# MCU.net
KiCad netlist of a schematic drawn in Altium Designer
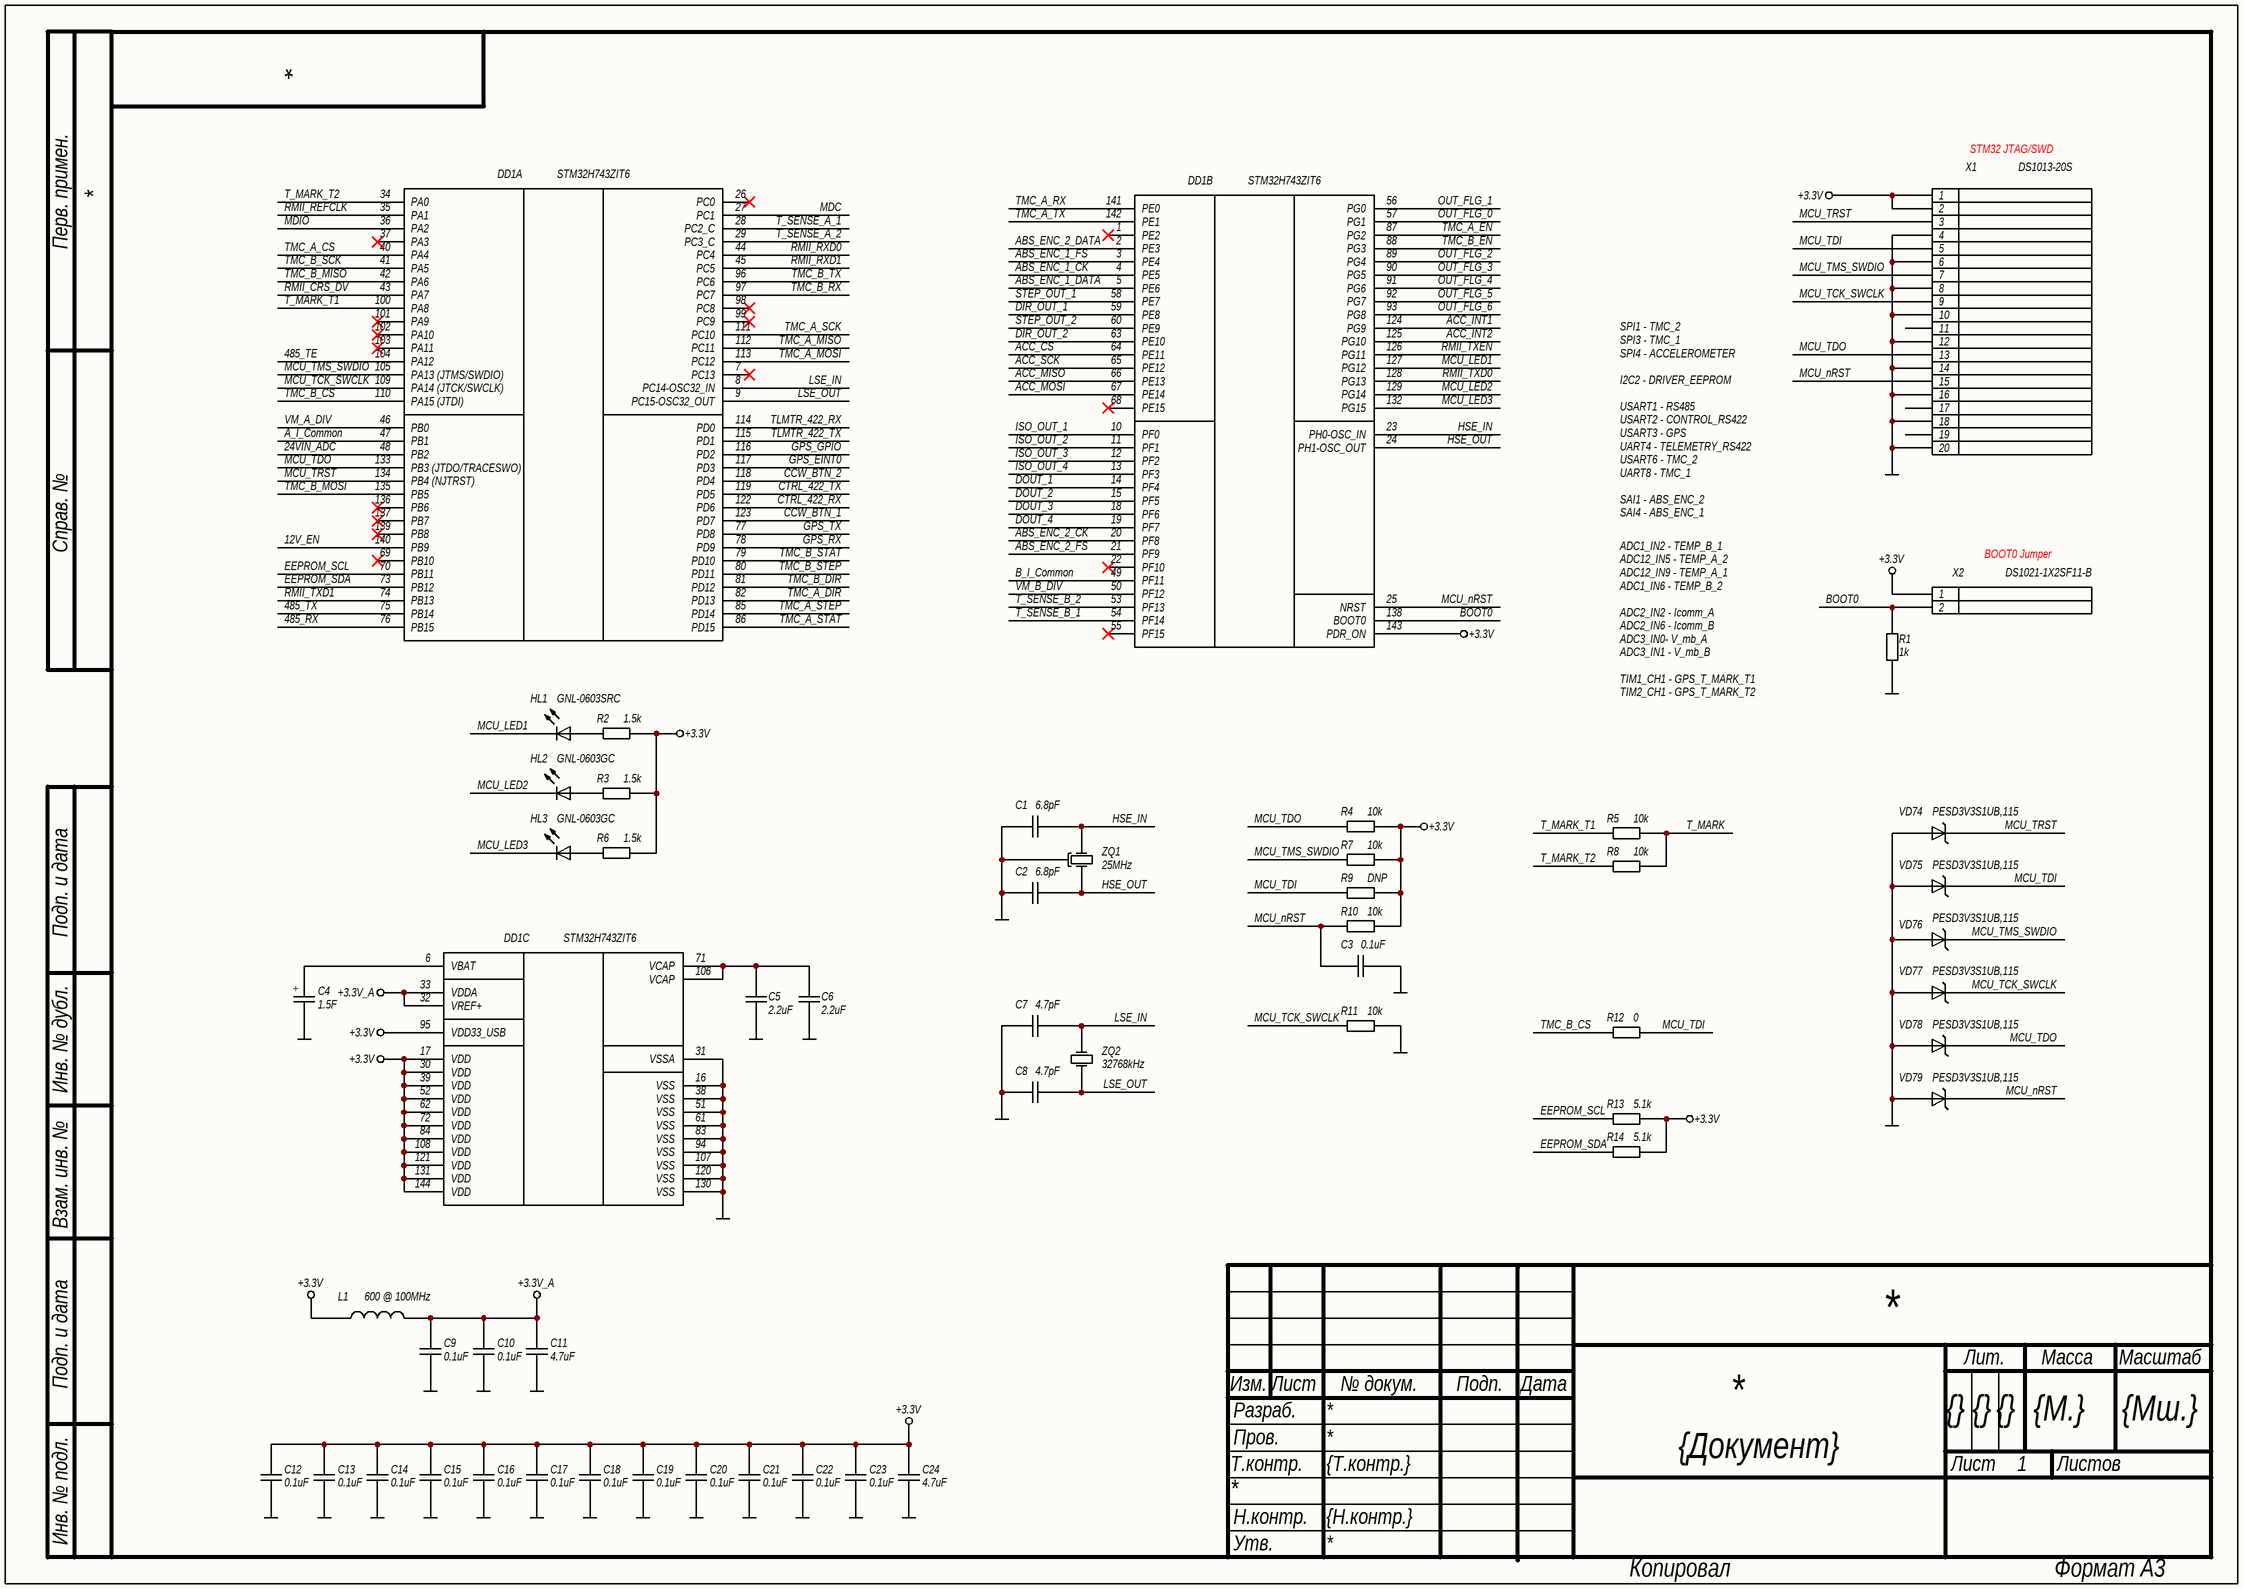
[diagram p0: MCU.SchDoc]

(export (version "E")
  (design (tool "Eeschema 10.0.6"))
  (components
    (comp (ref "C1")
      (value "6.8pF")
      (footprint "C0603N")
      (description "Конденсатор")
      (libsource (lib "Components Library") (part "CAP_FIXED"))
    )
    (comp (ref "C2")
      (value "6.8pF")
      (footprint "C0603N")
      (description "Конденсатор")
      (libsource (lib "Components Library") (part "CAP_FIXED"))
    )
    (comp (ref "C3")
      (value "0.1uF")
      (footprint "C0603N")
      (description "Конденсатор")
      (libsource (lib "Components Library") (part "CAP_FIXED"))
    )
    (comp (ref "C4")
      (value "1.5F")
      (footprint "KR-5R5H155-R")
      (description "Ионистор")
      (libsource (lib "Components Library") (part "CAP_EDLC"))
    )
    (comp (ref "C5")
      (value "2.2uF")
      (footprint "C0603N")
      (description "Конденсатор")
      (libsource (lib "Components Library") (part "CAP_FIXED"))
    )
    (comp (ref "C6")
      (value "2.2uF")
      (footprint "C0603N")
      (description "Конденсатор")
      (libsource (lib "Components Library") (part "CAP_FIXED"))
    )
    (comp (ref "C7")
      (value "4.7pF")
      (footprint "C0603N")
      (description "Конденсатор")
      (libsource (lib "Components Library") (part "CAP_FIXED"))
    )
    (comp (ref "C8")
      (value "4.7pF")
      (footprint "C0603N")
      (description "Конденсатор")
      (libsource (lib "Components Library") (part "CAP_FIXED"))
    )
    (comp (ref "C9")
      (value "0.1uF")
      (footprint "C0603N")
      (description "Конденсатор")
      (libsource (lib "Components Library") (part "CAP_FIXED"))
    )
    (comp (ref "C10")
      (value "0.1uF")
      (footprint "C0603N")
      (description "Конденсатор")
      (libsource (lib "Components Library") (part "CAP_FIXED"))
    )
    (comp (ref "C11")
      (value "4.7uF")
      (footprint "C0603N")
      (description "Конденсатор")
      (libsource (lib "Components Library") (part "CAP_FIXED"))
    )
    (comp (ref "C12")
      (value "0.1uF")
      (footprint "C0603N")
      (description "Конденсатор")
      (libsource (lib "Components Library") (part "CAP_FIXED"))
    )
    (comp (ref "C13")
      (value "0.1uF")
      (footprint "C0603N")
      (description "Конденсатор")
      (libsource (lib "Components Library") (part "CAP_FIXED"))
    )
    (comp (ref "C14")
      (value "0.1uF")
      (footprint "C0603N")
      (description "Конденсатор")
      (libsource (lib "Components Library") (part "CAP_FIXED"))
    )
    (comp (ref "C15")
      (value "0.1uF")
      (footprint "C0603N")
      (description "Конденсатор")
      (libsource (lib "Components Library") (part "CAP_FIXED"))
    )
    (comp (ref "C16")
      (value "0.1uF")
      (footprint "C0603N")
      (description "Конденсатор")
      (libsource (lib "Components Library") (part "CAP_FIXED"))
    )
    (comp (ref "C17")
      (value "0.1uF")
      (footprint "C0603N")
      (description "Конденсатор")
      (libsource (lib "Components Library") (part "CAP_FIXED"))
    )
    (comp (ref "C18")
      (value "0.1uF")
      (footprint "C0603N")
      (description "Конденсатор")
      (libsource (lib "Components Library") (part "CAP_FIXED"))
    )
    (comp (ref "C19")
      (value "0.1uF")
      (footprint "C0603N")
      (description "Конденсатор")
      (libsource (lib "Components Library") (part "CAP_FIXED"))
    )
    (comp (ref "C20")
      (value "0.1uF")
      (footprint "C0603N")
      (description "Конденсатор")
      (libsource (lib "Components Library") (part "CAP_FIXED"))
    )
    (comp (ref "C21")
      (value "0.1uF")
      (footprint "C0603N")
      (description "Конденсатор")
      (libsource (lib "Components Library") (part "CAP_FIXED"))
    )
    (comp (ref "C22")
      (value "0.1uF")
      (footprint "C0603N")
      (description "Конденсатор")
      (libsource (lib "Components Library") (part "CAP_FIXED"))
    )
    (comp (ref "C23")
      (value "0.1uF")
      (footprint "C0603N")
      (description "Конденсатор")
      (libsource (lib "Components Library") (part "CAP_FIXED"))
    )
    (comp (ref "C24")
      (value "4.7uF")
      (footprint "C0603N")
      (description "Конденсатор")
      (libsource (lib "Components Library") (part "CAP_FIXED"))
    )
    (comp (ref "DD1")
      (value "STM32H743ZIT6")
      (footprint "LQFP144")
      (description "Микросхема микроконтроллер")
      (libsource (lib "Components Library") (part "STM32H743ZxT"))
    )
    (comp (ref "HL1")
      (value "GNL-0603SRC")
      (footprint "LED0603")
      (description "Светодиод")
      (libsource (lib "Components Library") (part "LED"))
    )
    (comp (ref "HL2")
      (value "GNL-0603GC")
      (footprint "LED0603")
      (description "Светодиод")
      (libsource (lib "Components Library") (part "LED"))
    )
    (comp (ref "HL3")
      (value "GNL-0603GC")
      (footprint "LED0603")
      (description "Светодиод")
      (libsource (lib "Components Library") (part "LED"))
    )
    (comp (ref "L1")
      (value "600 @ 100MHz")
      (footprint "FB0603N")
      (description "Фильтр ЭМП индуктивный")
      (libsource (lib "Components Library") (part "IND_FILTER"))
    )
    (comp (ref "R1")
      (value "1k")
      (footprint "R0603N")
      (description "Резистор")
      (libsource (lib "") (part "RES_FIXED_1"))
    )
    (comp (ref "R2")
      (value "1.5k")
      (footprint "R0603N")
      (description "Резистор")
      (libsource (lib "Components Library") (part "RES_FIXED"))
    )
    (comp (ref "R3")
      (value "1.5k")
      (footprint "R0603N")
      (description "Резистор")
      (libsource (lib "Components Library") (part "RES_FIXED"))
    )
    (comp (ref "R4")
      (value "10k")
      (footprint "R0603N")
      (description "Резистор")
      (libsource (lib "Components Library") (part "RES_FIXED"))
    )
    (comp (ref "R5")
      (value "10k")
      (footprint "R0603N")
      (description "Резистор")
      (libsource (lib "") (part "RES_FIXED_2"))
    )
    (comp (ref "R6")
      (value "1.5k")
      (footprint "R0603N")
      (description "Резистор")
      (libsource (lib "Components Library") (part "RES_FIXED"))
    )
    (comp (ref "R7")
      (value "10k")
      (footprint "R0603N")
      (description "Резистор")
      (libsource (lib "Components Library") (part "RES_FIXED"))
    )
    (comp (ref "R8")
      (value "10k")
      (footprint "R0603N")
      (description "Резистор")
      (libsource (lib "") (part "RES_FIXED_2"))
    )
    (comp (ref "R9")
      (value "DNP")
      (footprint "R0603N")
      (description "Резистор")
      (libsource (lib "Components Library") (part "RES_FIXED"))
    )
    (comp (ref "R10")
      (value "10k")
      (footprint "R0603N")
      (description "Резистор")
      (libsource (lib "Components Library") (part "RES_FIXED"))
    )
    (comp (ref "R11")
      (value "10k")
      (footprint "R0603N")
      (description "Резистор")
      (libsource (lib "") (part "RES_FIXED_3"))
    )
    (comp (ref "R12")
      (value "0")
      (footprint "R0603N")
      (description "Резистор")
      (libsource (lib "") (part "RES_FIXED_1"))
    )
    (comp (ref "R13")
      (value "5.1k")
      (footprint "R0603N")
      (description "Резистор")
      (libsource (lib "Components Library") (part "RES_FIXED"))
    )
    (comp (ref "R14")
      (value "5.1k")
      (footprint "R0603N")
      (description "Резистор")
      (libsource (lib "Components Library") (part "RES_FIXED"))
    )
    (comp (ref "VD74")
      (value "PESD3V3S1UB,115")
      (footprint "SOD523")
      (description "TVS диод однонаправлвенный")
      (libsource (lib "Components Library") (part "TVS_UNIDIR"))
    )
    (comp (ref "VD75")
      (value "PESD3V3S1UB,115")
      (footprint "SOD523")
      (description "TVS диод однонаправлвенный")
      (libsource (lib "Components Library") (part "TVS_UNIDIR"))
    )
    (comp (ref "VD76")
      (value "PESD3V3S1UB,115")
      (footprint "SOD523")
      (description "TVS диод однонаправлвенный")
      (libsource (lib "Components Library") (part "TVS_UNIDIR"))
    )
    (comp (ref "VD77")
      (value "PESD3V3S1UB,115")
      (footprint "SOD523")
      (description "TVS диод однонаправлвенный")
      (libsource (lib "Components Library") (part "TVS_UNIDIR"))
    )
    (comp (ref "VD78")
      (value "PESD3V3S1UB,115")
      (footprint "SOD523")
      (description "TVS диод однонаправлвенный")
      (libsource (lib "Components Library") (part "TVS_UNIDIR"))
    )
    (comp (ref "VD79")
      (value "PESD3V3S1UB,115")
      (footprint "SOD523")
      (description "TVS диод однонаправлвенный")
      (libsource (lib "Components Library") (part "TVS_UNIDIR"))
    )
    (comp (ref "X1")
      (value "DS1013-20S")
      (footprint "2.54_2X10_HEADER_BOX")
      (description "Разъем, 20 контактов")
      (libsource (lib "Components Library") (part "Connector 20"))
    )
    (comp (ref "X2")
      (value "DS1021-1X2SF11-B")
      (footprint "2.54_2X1_HEADER")
      (description "Разъем, 2 контакта")
      (libsource (lib "Components Library") (part "Connector 2"))
    )
    (comp (ref "ZQ1")
      (value "25MHz")
      (footprint "NX3225GA")
      (description "Кварцевый резонатор, экранированный")
      (libsource (lib "Components Library") (part "RESONATOR_3PIN"))
    )
    (comp (ref "ZQ2")
      (value "32768kHz")
      (footprint "NX3215SA")
      (description "Кварцевый резонатор")
      (libsource (lib "Components Library") (part "RESONATOR"))
    )
  )
  (nets
    (net (code "1") (name "+3.3V") (class "Default")
      (node (ref "C12") (pin "2") (pinfunction "2_2") (pintype "passive"))
      (node (ref "C13") (pin "2") (pinfunction "2_2") (pintype "passive"))
      (node (ref "C14") (pin "2") (pinfunction "2_2") (pintype "passive"))
      (node (ref "C15") (pin "2") (pinfunction "2_2") (pintype "passive"))
      (node (ref "C16") (pin "2") (pinfunction "2_2") (pintype "passive"))
      (node (ref "C17") (pin "2") (pinfunction "2_2") (pintype "passive"))
      (node (ref "C18") (pin "2") (pinfunction "2_2") (pintype "passive"))
      (node (ref "C19") (pin "2") (pinfunction "2_2") (pintype "passive"))
      (node (ref "C20") (pin "2") (pinfunction "2_2") (pintype "passive"))
      (node (ref "C21") (pin "2") (pinfunction "2_2") (pintype "passive"))
      (node (ref "C22") (pin "2") (pinfunction "2_2") (pintype "passive"))
      (node (ref "C23") (pin "2") (pinfunction "2_2") (pintype "passive"))
      (node (ref "C24") (pin "2") (pinfunction "2_2") (pintype "passive"))
      (node (ref "DD1") (pin "108") (pinfunction "VDD_108") (pintype "power_in"))
      (node (ref "DD1") (pin "121") (pinfunction "VDD_121") (pintype "power_in"))
      (node (ref "DD1") (pin "131") (pinfunction "VDD_131") (pintype "power_in"))
      (node (ref "DD1") (pin "143") (pinfunction "PDR_ON_143") (pintype "power_in"))
      (node (ref "DD1") (pin "144") (pinfunction "VDD_144") (pintype "power_in"))
      (node (ref "DD1") (pin "17") (pinfunction "VDD_17") (pintype "power_in"))
      (node (ref "DD1") (pin "30") (pinfunction "VDD_30") (pintype "power_in"))
      (node (ref "DD1") (pin "39") (pinfunction "VDD_39") (pintype "power_in"))
      (node (ref "DD1") (pin "52") (pinfunction "VDD_52") (pintype "power_in"))
      (node (ref "DD1") (pin "62") (pinfunction "VDD_62") (pintype "power_in"))
      (node (ref "DD1") (pin "72") (pinfunction "VDD_72") (pintype "power_in"))
      (node (ref "DD1") (pin "84") (pinfunction "VDD_84") (pintype "power_in"))
      (node (ref "DD1") (pin "95") (pinfunction "VDD33_USB_95") (pintype "power_in"))
      (node (ref "L1") (pin "1") (pinfunction "1_1") (pintype "passive"))
      (node (ref "R10") (pin "1") (pinfunction "1_1") (pintype "passive"))
      (node (ref "R13") (pin "1") (pinfunction "1_1") (pintype "passive"))
      (node (ref "R14") (pin "1") (pinfunction "1_1") (pintype "passive"))
      (node (ref "R2") (pin "1") (pinfunction "1_1") (pintype "passive"))
      (node (ref "R3") (pin "1") (pinfunction "1_1") (pintype "passive"))
      (node (ref "R4") (pin "1") (pinfunction "1_1") (pintype "passive"))
      (node (ref "R6") (pin "1") (pinfunction "1_1") (pintype "passive"))
      (node (ref "R7") (pin "1") (pinfunction "1_1") (pintype "passive"))
      (node (ref "R9") (pin "1") (pinfunction "1_1") (pintype "passive"))
      (node (ref "X1") (pin "1") (pinfunction "1_1") (pintype "power_in"))
      (node (ref "X1") (pin "2") (pinfunction "2_2") (pintype "power_in"))
      (node (ref "X2") (pin "1") (pinfunction "1_1") (pintype "power_in"))
    )
    (net (code "2") (name "+3.3V_A") (class "Default")
      (node (ref "C10") (pin "2") (pinfunction "2_2") (pintype "passive"))
      (node (ref "C11") (pin "2") (pinfunction "2_2") (pintype "passive"))
      (node (ref "C9") (pin "2") (pinfunction "2_2") (pintype "passive"))
      (node (ref "DD1") (pin "32") (pinfunction "VREF+_32") (pintype "power_in"))
      (node (ref "DD1") (pin "33") (pinfunction "VDDA_33") (pintype "power_in"))
      (node (ref "L1") (pin "2") (pinfunction "2_2") (pintype "passive"))
    )
    (net (code "3") (name "/12V_EN") (class "Default")
      (node (ref "DD1") (pin "140") (pinfunction "PB9_140") (pintype "power_in"))
    )
    (net (code "4") (name "/24VIN_ADC") (class "Default")
      (node (ref "DD1") (pin "48") (pinfunction "PB2_48") (pintype "power_in"))
    )
    (net (code "5") (name "/485_RX") (class "Default")
      (node (ref "DD1") (pin "76") (pinfunction "PB15_76") (pintype "power_in"))
    )
    (net (code "6") (name "/485_TE") (class "Default")
      (node (ref "DD1") (pin "104") (pinfunction "PA12_104") (pintype "power_in"))
    )
    (net (code "7") (name "/485_TX") (class "Default")
      (node (ref "DD1") (pin "75") (pinfunction "PB14_75") (pintype "power_in"))
    )
    (net (code "8") (name "/ABS_ENC_1_CK") (class "Default")
      (node (ref "DD1") (pin "4") (pinfunction "PE5_4") (pintype "power_in"))
    )
    (net (code "9") (name "/ABS_ENC_1_DATA") (class "Default")
      (node (ref "DD1") (pin "5") (pinfunction "PE6_5") (pintype "power_in"))
    )
    (net (code "10") (name "/ABS_ENC_1_FS") (class "Default")
      (node (ref "DD1") (pin "3") (pinfunction "PE4_3") (pintype "power_in"))
    )
    (net (code "11") (name "/ABS_ENC_2_CK") (class "Default")
      (node (ref "DD1") (pin "20") (pinfunction "PF8_20") (pintype "power_in"))
    )
    (net (code "12") (name "/ABS_ENC_2_DATA") (class "Default")
      (node (ref "DD1") (pin "2") (pinfunction "PE3_2") (pintype "power_in"))
    )
    (net (code "13") (name "/ABS_ENC_2_FS") (class "Default")
      (node (ref "DD1") (pin "21") (pinfunction "PF9_21") (pintype "power_in"))
    )
    (net (code "14") (name "/ACC_CS") (class "Default")
      (node (ref "DD1") (pin "64") (pinfunction "PE11_64") (pintype "power_in"))
    )
    (net (code "15") (name "/ACC_INT1") (class "Default")
      (node (ref "DD1") (pin "124") (pinfunction "PG9_124") (pintype "power_in"))
    )
    (net (code "16") (name "/ACC_INT2") (class "Default")
      (node (ref "DD1") (pin "125") (pinfunction "PG10_125") (pintype "power_in"))
    )
    (net (code "17") (name "/ACC_MISO") (class "Default")
      (node (ref "DD1") (pin "66") (pinfunction "PE13_66") (pintype "power_in"))
    )
    (net (code "18") (name "/ACC_MOSI") (class "Default")
      (node (ref "DD1") (pin "67") (pinfunction "PE14_67") (pintype "power_in"))
    )
    (net (code "19") (name "/ACC_SCK") (class "Default")
      (node (ref "DD1") (pin "65") (pinfunction "PE12_65") (pintype "power_in"))
    )
    (net (code "20") (name "/A_I_Common") (class "Default")
      (node (ref "DD1") (pin "47") (pinfunction "PB1_47") (pintype "power_in"))
    )
    (net (code "21") (name "/BOOT0") (class "Default")
      (node (ref "DD1") (pin "138") (pinfunction "BOOT0_138") (pintype "power_in"))
      (node (ref "R1") (pin "1") (pinfunction "1_1") (pintype "passive"))
      (node (ref "X2") (pin "2") (pinfunction "2_2") (pintype "power_in"))
    )
    (net (code "22") (name "/B_I_Common") (class "Default")
      (node (ref "DD1") (pin "49") (pinfunction "PF11_49") (pintype "power_in"))
    )
    (net (code "23") (name "/CCW_BTN_1") (class "Default")
      (node (ref "DD1") (pin "123") (pinfunction "PD7_123") (pintype "power_in"))
    )
    (net (code "24") (name "/CCW_BTN_2") (class "Default")
      (node (ref "DD1") (pin "118") (pinfunction "PD4_118") (pintype "power_in"))
    )
    (net (code "25") (name "/CTRL_422_RX") (class "Default")
      (node (ref "DD1") (pin "122") (pinfunction "PD6_122") (pintype "power_in"))
    )
    (net (code "26") (name "/CTRL_422_TX") (class "Default")
      (node (ref "DD1") (pin "119") (pinfunction "PD5_119") (pintype "power_in"))
    )
    (net (code "27") (name "/DIR_OUT_1") (class "Default")
      (node (ref "DD1") (pin "59") (pinfunction "PE8_59") (pintype "power_in"))
    )
    (net (code "28") (name "/DIR_OUT_2") (class "Default")
      (node (ref "DD1") (pin "63") (pinfunction "PE10_63") (pintype "power_in"))
    )
    (net (code "29") (name "/DOUT_1") (class "Default")
      (node (ref "DD1") (pin "14") (pinfunction "PF4_14") (pintype "power_in"))
    )
    (net (code "30") (name "/DOUT_2") (class "Default")
      (node (ref "DD1") (pin "15") (pinfunction "PF5_15") (pintype "power_in"))
    )
    (net (code "31") (name "/DOUT_3") (class "Default")
      (node (ref "DD1") (pin "18") (pinfunction "PF6_18") (pintype "power_in"))
    )
    (net (code "32") (name "/DOUT_4") (class "Default")
      (node (ref "DD1") (pin "19") (pinfunction "PF7_19") (pintype "power_in"))
    )
    (net (code "33") (name "/EEPROM_SCL") (class "Default")
      (node (ref "DD1") (pin "70") (pinfunction "PB11_70") (pintype "power_in"))
      (node (ref "R13") (pin "2") (pinfunction "2_2") (pintype "passive"))
    )
    (net (code "34") (name "/EEPROM_SDA") (class "Default")
      (node (ref "DD1") (pin "73") (pinfunction "PB12_73") (pintype "power_in"))
      (node (ref "R14") (pin "2") (pinfunction "2_2") (pintype "passive"))
    )
    (net (code "35") (name "/GPS_EINT0") (class "Default")
      (node (ref "DD1") (pin "117") (pinfunction "PD3_117") (pintype "power_in"))
    )
    (net (code "36") (name "/GPS_GPIO") (class "Default")
      (node (ref "DD1") (pin "116") (pinfunction "PD2_116") (pintype "power_in"))
    )
    (net (code "37") (name "/GPS_RX") (class "Default")
      (node (ref "DD1") (pin "78") (pinfunction "PD9_78") (pintype "power_in"))
    )
    (net (code "38") (name "/GPS_TX") (class "Default")
      (node (ref "DD1") (pin "77") (pinfunction "PD8_77") (pintype "power_in"))
    )
    (net (code "39") (name "/HSE_IN") (class "Default")
      (node (ref "C1") (pin "1") (pinfunction "1_1") (pintype "passive"))
      (node (ref "DD1") (pin "23") (pinfunction "PH0-OSC_IN_23") (pintype "power_in"))
      (node (ref "ZQ1") (pin "1") (pinfunction "1_1") (pintype "passive"))
    )
    (net (code "40") (name "/HSE_OUT") (class "Default")
      (node (ref "C2") (pin "1") (pinfunction "1_1") (pintype "passive"))
      (node (ref "DD1") (pin "24") (pinfunction "PH1-OSC_OUT_24") (pintype "power_in"))
      (node (ref "ZQ1") (pin "3") (pinfunction "3_3") (pintype "passive"))
    )
    (net (code "41") (name "/ISO_OUT_1") (class "Default")
      (node (ref "DD1") (pin "10") (pinfunction "PF0_10") (pintype "power_in"))
    )
    (net (code "42") (name "/ISO_OUT_2") (class "Default")
      (node (ref "DD1") (pin "11") (pinfunction "PF1_11") (pintype "power_in"))
    )
    (net (code "43") (name "/ISO_OUT_3") (class "Default")
      (node (ref "DD1") (pin "12") (pinfunction "PF2_12") (pintype "power_in"))
    )
    (net (code "44") (name "/ISO_OUT_4") (class "Default")
      (node (ref "DD1") (pin "13") (pinfunction "PF3_13") (pintype "power_in"))
    )
    (net (code "45") (name "/LSE_IN") (class "Default")
      (node (ref "C7") (pin "1") (pinfunction "1_1") (pintype "passive"))
      (node (ref "DD1") (pin "8") (pinfunction "PC14-OSC32_IN_8") (pintype "power_in"))
      (node (ref "ZQ2") (pin "2") (pinfunction "2_2") (pintype "passive"))
    )
    (net (code "46") (name "/LSE_OUT") (class "Default")
      (node (ref "C8") (pin "1") (pinfunction "1_1") (pintype "passive"))
      (node (ref "DD1") (pin "9") (pinfunction "PC15-OSC32_OUT_9") (pintype "power_in"))
      (node (ref "ZQ2") (pin "1") (pinfunction "1_1") (pintype "passive"))
    )
    (net (code "47") (name "/MCU_LED1") (class "Default")
      (node (ref "DD1") (pin "127") (pinfunction "PG12_127") (pintype "power_in"))
      (node (ref "HL1") (pin "1") (pinfunction "K_1") (pintype "passive"))
    )
    (net (code "48") (name "/MCU_LED2") (class "Default")
      (node (ref "DD1") (pin "129") (pinfunction "PG14_129") (pintype "power_in"))
      (node (ref "HL2") (pin "1") (pinfunction "K_1") (pintype "passive"))
    )
    (net (code "49") (name "/MCU_LED3") (class "Default")
      (node (ref "DD1") (pin "132") (pinfunction "PG15_132") (pintype "power_in"))
      (node (ref "HL3") (pin "1") (pinfunction "K_1") (pintype "passive"))
    )
    (net (code "50") (name "/MCU_TCK_SWCLK") (class "Default")
      (node (ref "DD1") (pin "109") (pinfunction "PA14_(JTCK/SWCLK)_109") (pintype "power_in"))
      (node (ref "R11") (pin "1") (pinfunction "1_1") (pintype "passive"))
      (node (ref "VD77") (pin "1") (pinfunction "K_1") (pintype "passive"))
      (node (ref "X1") (pin "9") (pinfunction "9_9") (pintype "power_in"))
    )
    (net (code "51") (name "/MCU_TDI") (class "Default")
      (node (ref "R12") (pin "1") (pinfunction "1_1") (pintype "passive"))
      (node (ref "R9") (pin "2") (pinfunction "2_2") (pintype "passive"))
      (node (ref "VD75") (pin "1") (pinfunction "K_1") (pintype "passive"))
      (node (ref "X1") (pin "5") (pinfunction "5_5") (pintype "power_in"))
    )
    (net (code "52") (name "/MCU_TDO") (class "Default")
      (node (ref "DD1") (pin "133") (pinfunction "PB3_(JTDO/TRACESWO)_133") (pintype "power_in"))
      (node (ref "R4") (pin "2") (pinfunction "2_2") (pintype "passive"))
      (node (ref "VD78") (pin "1") (pinfunction "K_1") (pintype "passive"))
      (node (ref "X1") (pin "13") (pinfunction "13_13") (pintype "power_in"))
    )
    (net (code "53") (name "/MCU_TMS_SWDIO") (class "Default")
      (node (ref "DD1") (pin "105") (pinfunction "PA13_(JTMS/SWDIO)_105") (pintype "power_in"))
      (node (ref "R7") (pin "2") (pinfunction "2_2") (pintype "passive"))
      (node (ref "VD76") (pin "1") (pinfunction "K_1") (pintype "passive"))
      (node (ref "X1") (pin "7") (pinfunction "7_7") (pintype "power_in"))
    )
    (net (code "54") (name "/MCU_TRST") (class "Default")
      (node (ref "DD1") (pin "134") (pinfunction "PB4_(NJTRST)_134") (pintype "power_in"))
      (node (ref "VD74") (pin "1") (pinfunction "K_1") (pintype "passive"))
      (node (ref "X1") (pin "3") (pinfunction "3_3") (pintype "power_in"))
    )
    (net (code "55") (name "/MCU_nRST") (class "Default")
      (node (ref "C3") (pin "2") (pinfunction "2_2") (pintype "passive"))
      (node (ref "DD1") (pin "25") (pinfunction "NRST_25") (pintype "power_in"))
      (node (ref "R10") (pin "2") (pinfunction "2_2") (pintype "passive"))
      (node (ref "VD79") (pin "1") (pinfunction "K_1") (pintype "passive"))
      (node (ref "X1") (pin "15") (pinfunction "15_15") (pintype "power_in"))
    )
    (net (code "56") (name "/MDC") (class "Default")
      (node (ref "DD1") (pin "27") (pinfunction "PC1_27") (pintype "power_in"))
    )
    (net (code "57") (name "/MDIO") (class "Default")
      (node (ref "DD1") (pin "36") (pinfunction "PA2_36") (pintype "power_in"))
    )
    (net (code "58") (name "/OUT_FLG_0") (class "Default")
      (node (ref "DD1") (pin "57") (pinfunction "PG1_57") (pintype "power_in"))
    )
    (net (code "59") (name "/OUT_FLG_1") (class "Default")
      (node (ref "DD1") (pin "56") (pinfunction "PG0_56") (pintype "power_in"))
    )
    (net (code "60") (name "/OUT_FLG_2") (class "Default")
      (node (ref "DD1") (pin "89") (pinfunction "PG4_89") (pintype "power_in"))
    )
    (net (code "61") (name "/OUT_FLG_3") (class "Default")
      (node (ref "DD1") (pin "90") (pinfunction "PG5_90") (pintype "power_in"))
    )
    (net (code "62") (name "/OUT_FLG_4") (class "Default")
      (node (ref "DD1") (pin "91") (pinfunction "PG6_91") (pintype "power_in"))
    )
    (net (code "63") (name "/OUT_FLG_5") (class "Default")
      (node (ref "DD1") (pin "92") (pinfunction "PG7_92") (pintype "power_in"))
    )
    (net (code "64") (name "/OUT_FLG_6") (class "Default")
      (node (ref "DD1") (pin "93") (pinfunction "PG8_93") (pintype "power_in"))
    )
    (net (code "65") (name "/RMII_CRS_DV") (class "Default")
      (node (ref "DD1") (pin "43") (pinfunction "PA7_43") (pintype "power_in"))
    )
    (net (code "66") (name "/RMII_REFCLK") (class "Default")
      (node (ref "DD1") (pin "35") (pinfunction "PA1_35") (pintype "power_in"))
    )
    (net (code "67") (name "/RMII_RXD0") (class "Default")
      (node (ref "DD1") (pin "44") (pinfunction "PC4_44") (pintype "power_in"))
    )
    (net (code "68") (name "/RMII_RXD1") (class "Default")
      (node (ref "DD1") (pin "45") (pinfunction "PC5_45") (pintype "power_in"))
    )
    (net (code "69") (name "/RMII_TXD0") (class "Default")
      (node (ref "DD1") (pin "128") (pinfunction "PG13_128") (pintype "power_in"))
    )
    (net (code "70") (name "/RMII_TXD1") (class "Default")
      (node (ref "DD1") (pin "74") (pinfunction "PB13_74") (pintype "power_in"))
    )
    (net (code "71") (name "/RMII_TXEN") (class "Default")
      (node (ref "DD1") (pin "126") (pinfunction "PG11_126") (pintype "power_in"))
    )
    (net (code "72") (name "/STEP_OUT_1") (class "Default")
      (node (ref "DD1") (pin "58") (pinfunction "PE7_58") (pintype "power_in"))
    )
    (net (code "73") (name "/STEP_OUT_2") (class "Default")
      (node (ref "DD1") (pin "60") (pinfunction "PE9_60") (pintype "power_in"))
    )
    (net (code "74") (name "/TLMTR_422_RX") (class "Default")
      (node (ref "DD1") (pin "114") (pinfunction "PD0_114") (pintype "power_in"))
    )
    (net (code "75") (name "/TLMTR_422_TX") (class "Default")
      (node (ref "DD1") (pin "115") (pinfunction "PD1_115") (pintype "power_in"))
    )
    (net (code "76") (name "/TMC_A_CS") (class "Default")
      (node (ref "DD1") (pin "40") (pinfunction "PA4_40") (pintype "power_in"))
    )
    (net (code "77") (name "/TMC_A_DIR") (class "Default")
      (node (ref "DD1") (pin "82") (pinfunction "PD13_82") (pintype "power_in"))
    )
    (net (code "78") (name "/TMC_A_EN") (class "Default")
      (node (ref "DD1") (pin "87") (pinfunction "PG2_87") (pintype "power_in"))
    )
    (net (code "79") (name "/TMC_A_MISO") (class "Default")
      (node (ref "DD1") (pin "112") (pinfunction "PC11_112") (pintype "power_in"))
    )
    (net (code "80") (name "/TMC_A_MOSI") (class "Default")
      (node (ref "DD1") (pin "113") (pinfunction "PC12_113") (pintype "power_in"))
    )
    (net (code "81") (name "/TMC_A_RX") (class "Default")
      (node (ref "DD1") (pin "141") (pinfunction "PE0_141") (pintype "power_in"))
    )
    (net (code "82") (name "/TMC_A_SCK") (class "Default")
      (node (ref "DD1") (pin "111") (pinfunction "PC10_111") (pintype "power_in"))
    )
    (net (code "83") (name "/TMC_A_STAT") (class "Default")
      (node (ref "DD1") (pin "86") (pinfunction "PD15_86") (pintype "power_in"))
    )
    (net (code "84") (name "/TMC_A_STEP") (class "Default")
      (node (ref "DD1") (pin "85") (pinfunction "PD14_85") (pintype "power_in"))
    )
    (net (code "85") (name "/TMC_A_TX") (class "Default")
      (node (ref "DD1") (pin "142") (pinfunction "PE1_142") (pintype "power_in"))
    )
    (net (code "86") (name "/TMC_B_CS") (class "Default")
      (node (ref "DD1") (pin "110") (pinfunction "PA15_(JTDI)_110") (pintype "power_in"))
      (node (ref "R12") (pin "2") (pinfunction "2_2") (pintype "passive"))
    )
    (net (code "87") (name "/TMC_B_DIR") (class "Default")
      (node (ref "DD1") (pin "81") (pinfunction "PD12_81") (pintype "power_in"))
    )
    (net (code "88") (name "/TMC_B_EN") (class "Default")
      (node (ref "DD1") (pin "88") (pinfunction "PG3_88") (pintype "power_in"))
    )
    (net (code "89") (name "/TMC_B_MISO") (class "Default")
      (node (ref "DD1") (pin "42") (pinfunction "PA6_42") (pintype "power_in"))
    )
    (net (code "90") (name "/TMC_B_MOSI") (class "Default")
      (node (ref "DD1") (pin "135") (pinfunction "PB5_135") (pintype "power_in"))
    )
    (net (code "91") (name "/TMC_B_RX") (class "Default")
      (node (ref "DD1") (pin "97") (pinfunction "PC7_97") (pintype "power_in"))
    )
    (net (code "92") (name "/TMC_B_SCK") (class "Default")
      (node (ref "DD1") (pin "41") (pinfunction "PA5_41") (pintype "power_in"))
    )
    (net (code "93") (name "/TMC_B_STAT") (class "Default")
      (node (ref "DD1") (pin "79") (pinfunction "PD10_79") (pintype "power_in"))
    )
    (net (code "94") (name "/TMC_B_STEP") (class "Default")
      (node (ref "DD1") (pin "80") (pinfunction "PD11_80") (pintype "power_in"))
    )
    (net (code "95") (name "/TMC_B_TX") (class "Default")
      (node (ref "DD1") (pin "96") (pinfunction "PC6_96") (pintype "power_in"))
    )
    (net (code "96") (name "/T_MARK") (class "Default")
      (node (ref "R5") (pin "2") (pinfunction "2_2") (pintype "passive"))
      (node (ref "R8") (pin "2") (pinfunction "2_2") (pintype "passive"))
    )
    (net (code "97") (name "/T_MARK_T1") (class "Default")
      (node (ref "DD1") (pin "100") (pinfunction "PA8_100") (pintype "power_in"))
      (node (ref "R5") (pin "1") (pinfunction "1_1") (pintype "passive"))
    )
    (net (code "98") (name "/T_MARK_T2") (class "Default")
      (node (ref "DD1") (pin "34") (pinfunction "PA0_34") (pintype "power_in"))
      (node (ref "R8") (pin "1") (pinfunction "1_1") (pintype "passive"))
    )
    (net (code "99") (name "/T_SENSE_A_1") (class "Default")
      (node (ref "DD1") (pin "28") (pinfunction "PC2_C_28") (pintype "power_in"))
    )
    (net (code "100") (name "/T_SENSE_A_2") (class "Default")
      (node (ref "DD1") (pin "29") (pinfunction "PC3_C_29") (pintype "power_in"))
    )
    (net (code "101") (name "/T_SENSE_B_1") (class "Default")
      (node (ref "DD1") (pin "54") (pinfunction "PF14_54") (pintype "power_in"))
    )
    (net (code "102") (name "/T_SENSE_B_2") (class "Default")
      (node (ref "DD1") (pin "53") (pinfunction "PF13_53") (pintype "power_in"))
    )
    (net (code "103") (name "/VM_A_DIV") (class "Default")
      (node (ref "DD1") (pin "46") (pinfunction "PB0_46") (pintype "power_in"))
    )
    (net (code "104") (name "/VM_B_DIV") (class "Default")
      (node (ref "DD1") (pin "50") (pinfunction "PF12_50") (pintype "power_in"))
    )
    (net (code "105") (name "GND") (class "Default")
      (node (ref "C1") (pin "2") (pinfunction "2_2") (pintype "passive"))
      (node (ref "C10") (pin "1") (pinfunction "1_1") (pintype "passive"))
      (node (ref "C11") (pin "1") (pinfunction "1_1") (pintype "passive"))
      (node (ref "C12") (pin "1") (pinfunction "1_1") (pintype "passive"))
      (node (ref "C13") (pin "1") (pinfunction "1_1") (pintype "passive"))
      (node (ref "C14") (pin "1") (pinfunction "1_1") (pintype "passive"))
      (node (ref "C15") (pin "1") (pinfunction "1_1") (pintype "passive"))
      (node (ref "C16") (pin "1") (pinfunction "1_1") (pintype "passive"))
      (node (ref "C17") (pin "1") (pinfunction "1_1") (pintype "passive"))
      (node (ref "C18") (pin "1") (pinfunction "1_1") (pintype "passive"))
      (node (ref "C19") (pin "1") (pinfunction "1_1") (pintype "passive"))
      (node (ref "C2") (pin "2") (pinfunction "2_2") (pintype "passive"))
      (node (ref "C20") (pin "1") (pinfunction "1_1") (pintype "passive"))
      (node (ref "C21") (pin "1") (pinfunction "1_1") (pintype "passive"))
      (node (ref "C22") (pin "1") (pinfunction "1_1") (pintype "passive"))
      (node (ref "C23") (pin "1") (pinfunction "1_1") (pintype "passive"))
      (node (ref "C24") (pin "1") (pinfunction "1_1") (pintype "passive"))
      (node (ref "C3") (pin "1") (pinfunction "1_1") (pintype "passive"))
      (node (ref "C4") (pin "2") (pinfunction "2_2") (pintype "passive"))
      (node (ref "C5") (pin "1") (pinfunction "1_1") (pintype "passive"))
      (node (ref "C6") (pin "1") (pinfunction "1_1") (pintype "passive"))
      (node (ref "C7") (pin "2") (pinfunction "2_2") (pintype "passive"))
      (node (ref "C8") (pin "2") (pinfunction "2_2") (pintype "passive"))
      (node (ref "C9") (pin "1") (pinfunction "1_1") (pintype "passive"))
      (node (ref "DD1") (pin "107") (pinfunction "VSS_107") (pintype "power_in"))
      (node (ref "DD1") (pin "120") (pinfunction "VSS_120") (pintype "power_in"))
      (node (ref "DD1") (pin "130") (pinfunction "VSS_130") (pintype "power_in"))
      (node (ref "DD1") (pin "16") (pinfunction "VSS_16") (pintype "power_in"))
      (node (ref "DD1") (pin "31") (pinfunction "VSSA_31") (pintype "power_in"))
      (node (ref "DD1") (pin "38") (pinfunction "VSS_38") (pintype "power_in"))
      (node (ref "DD1") (pin "51") (pinfunction "VSS_51") (pintype "power_in"))
      (node (ref "DD1") (pin "61") (pinfunction "VSS_61") (pintype "power_in"))
      (node (ref "DD1") (pin "83") (pinfunction "VSS_83") (pintype "power_in"))
      (node (ref "DD1") (pin "94") (pinfunction "VSS_94") (pintype "power_in"))
      (node (ref "R1") (pin "2") (pinfunction "2_2") (pintype "passive"))
      (node (ref "R11") (pin "2") (pinfunction "2_2") (pintype "passive"))
      (node (ref "VD74") (pin "2") (pinfunction "A_2") (pintype "passive"))
      (node (ref "VD75") (pin "2") (pinfunction "A_2") (pintype "passive"))
      (node (ref "VD76") (pin "2") (pinfunction "A_2") (pintype "passive"))
      (node (ref "VD77") (pin "2") (pinfunction "A_2") (pintype "passive"))
      (node (ref "VD78") (pin "2") (pinfunction "A_2") (pintype "passive"))
      (node (ref "VD79") (pin "2") (pinfunction "A_2") (pintype "passive"))
      (node (ref "X1") (pin "10") (pinfunction "10_10") (pintype "power_in"))
      (node (ref "X1") (pin "12") (pinfunction "12_12") (pintype "power_in"))
      (node (ref "X1") (pin "14") (pinfunction "14_14") (pintype "power_in"))
      (node (ref "X1") (pin "16") (pinfunction "16_16") (pintype "power_in"))
      (node (ref "X1") (pin "18") (pinfunction "18_18") (pintype "power_in"))
      (node (ref "X1") (pin "20") (pinfunction "20_20") (pintype "power_in"))
      (node (ref "X1") (pin "4") (pinfunction "4_4") (pintype "power_in"))
      (node (ref "X1") (pin "6") (pinfunction "6_6") (pintype "power_in"))
      (node (ref "X1") (pin "8") (pinfunction "8_8") (pintype "power_in"))
      (node (ref "ZQ1") (pin "2") (pinfunction "2_2") (pintype "passive"))
    )
    (net (code "106") (name "Net-(C5-Pad2)") (class "Default")
      (node (ref "C5") (pin "2") (pinfunction "2_2") (pintype "passive"))
      (node (ref "C6") (pin "2") (pinfunction "2_2") (pintype "passive"))
      (node (ref "DD1") (pin "106") (pinfunction "VCAP_106") (pintype "power_in"))
      (node (ref "DD1") (pin "71") (pinfunction "VCAP_71") (pintype "power_in"))
    )
    (net (code "107") (name "Net-(DD1C-VBAT)") (class "Default")
      (node (ref "C4") (pin "1") (pinfunction "1_1") (pintype "passive"))
      (node (ref "DD1") (pin "6") (pinfunction "VBAT_6") (pintype "power_in"))
    )
    (net (code "108") (name "Net-(HL1-A)") (class "Default")
      (node (ref "HL1") (pin "2") (pinfunction "A_2") (pintype "passive"))
      (node (ref "R2") (pin "2") (pinfunction "2_2") (pintype "passive"))
    )
    (net (code "109") (name "Net-(HL2-A)") (class "Default")
      (node (ref "HL2") (pin "2") (pinfunction "A_2") (pintype "passive"))
      (node (ref "R3") (pin "2") (pinfunction "2_2") (pintype "passive"))
    )
    (net (code "110") (name "Net-(HL3-A)") (class "Default")
      (node (ref "HL3") (pin "2") (pinfunction "A_2") (pintype "passive"))
      (node (ref "R6") (pin "2") (pinfunction "2_2") (pintype "passive"))
    )
    (net (code "111") (name "unconnected-(DD1A-PA3-Pad37)") (class "Default")
      (node (ref "DD1") (pin "37") (pinfunction "PA3_37") (pintype "power_in+no_connect"))
    )
    (net (code "112") (name "unconnected-(DD1A-PA9-Pad101)") (class "Default")
      (node (ref "DD1") (pin "101") (pinfunction "PA9_101") (pintype "power_in+no_connect"))
    )
    (net (code "113") (name "unconnected-(DD1A-PA10-Pad102)") (class "Default")
      (node (ref "DD1") (pin "102") (pinfunction "PA10_102") (pintype "power_in+no_connect"))
    )
    (net (code "114") (name "unconnected-(DD1A-PA11-Pad103)") (class "Default")
      (node (ref "DD1") (pin "103") (pinfunction "PA11_103") (pintype "power_in+no_connect"))
    )
    (net (code "115") (name "unconnected-(DD1A-PB6-Pad136)") (class "Default")
      (node (ref "DD1") (pin "136") (pinfunction "PB6_136") (pintype "power_in+no_connect"))
    )
    (net (code "116") (name "unconnected-(DD1A-PB7-Pad137)") (class "Default")
      (node (ref "DD1") (pin "137") (pinfunction "PB7_137") (pintype "power_in+no_connect"))
    )
    (net (code "117") (name "unconnected-(DD1A-PB8-Pad139)") (class "Default")
      (node (ref "DD1") (pin "139") (pinfunction "PB8_139") (pintype "power_in+no_connect"))
    )
    (net (code "118") (name "unconnected-(DD1A-PB10-Pad69)") (class "Default")
      (node (ref "DD1") (pin "69") (pinfunction "PB10_69") (pintype "power_in+no_connect"))
    )
    (net (code "119") (name "unconnected-(DD1A-PC0-Pad26)") (class "Default")
      (node (ref "DD1") (pin "26") (pinfunction "PC0_26") (pintype "power_in+no_connect"))
    )
    (net (code "120") (name "unconnected-(DD1A-PC8-Pad98)") (class "Default")
      (node (ref "DD1") (pin "98") (pinfunction "PC8_98") (pintype "power_in+no_connect"))
    )
    (net (code "121") (name "unconnected-(DD1A-PC9-Pad99)") (class "Default")
      (node (ref "DD1") (pin "99") (pinfunction "PC9_99") (pintype "power_in+no_connect"))
    )
    (net (code "122") (name "unconnected-(DD1A-PC13-Pad7)") (class "Default")
      (node (ref "DD1") (pin "7") (pinfunction "PC13_7") (pintype "power_in+no_connect"))
    )
    (net (code "123") (name "unconnected-(DD1B-PE2-Pad1)") (class "Default")
      (node (ref "DD1") (pin "1") (pinfunction "PE2_1") (pintype "power_in+no_connect"))
    )
    (net (code "124") (name "unconnected-(DD1B-PE15-Pad68)") (class "Default")
      (node (ref "DD1") (pin "68") (pinfunction "PE15_68") (pintype "power_in+no_connect"))
    )
    (net (code "125") (name "unconnected-(DD1B-PF10-Pad22)") (class "Default")
      (node (ref "DD1") (pin "22") (pinfunction "PF10_22") (pintype "power_in+no_connect"))
    )
    (net (code "126") (name "unconnected-(DD1B-PF15-Pad55)") (class "Default")
      (node (ref "DD1") (pin "55") (pinfunction "PF15_55") (pintype "power_in+no_connect"))
    )
    (net (code "127") (name "unconnected-(X1-Pad11)") (class "Default")
      (node (ref "X1") (pin "11") (pinfunction "11_11") (pintype "power_in"))
    )
    (net (code "128") (name "unconnected-(X1-Pad17)") (class "Default")
      (node (ref "X1") (pin "17") (pinfunction "17_17") (pintype "power_in"))
    )
    (net (code "129") (name "unconnected-(X1-Pad19)") (class "Default")
      (node (ref "X1") (pin "19") (pinfunction "19_19") (pintype "power_in"))
    )
  )
)
